# Single_PCB_-_IRM-10-5.net
KiCad netlist of a schematic drawn in EAGLE
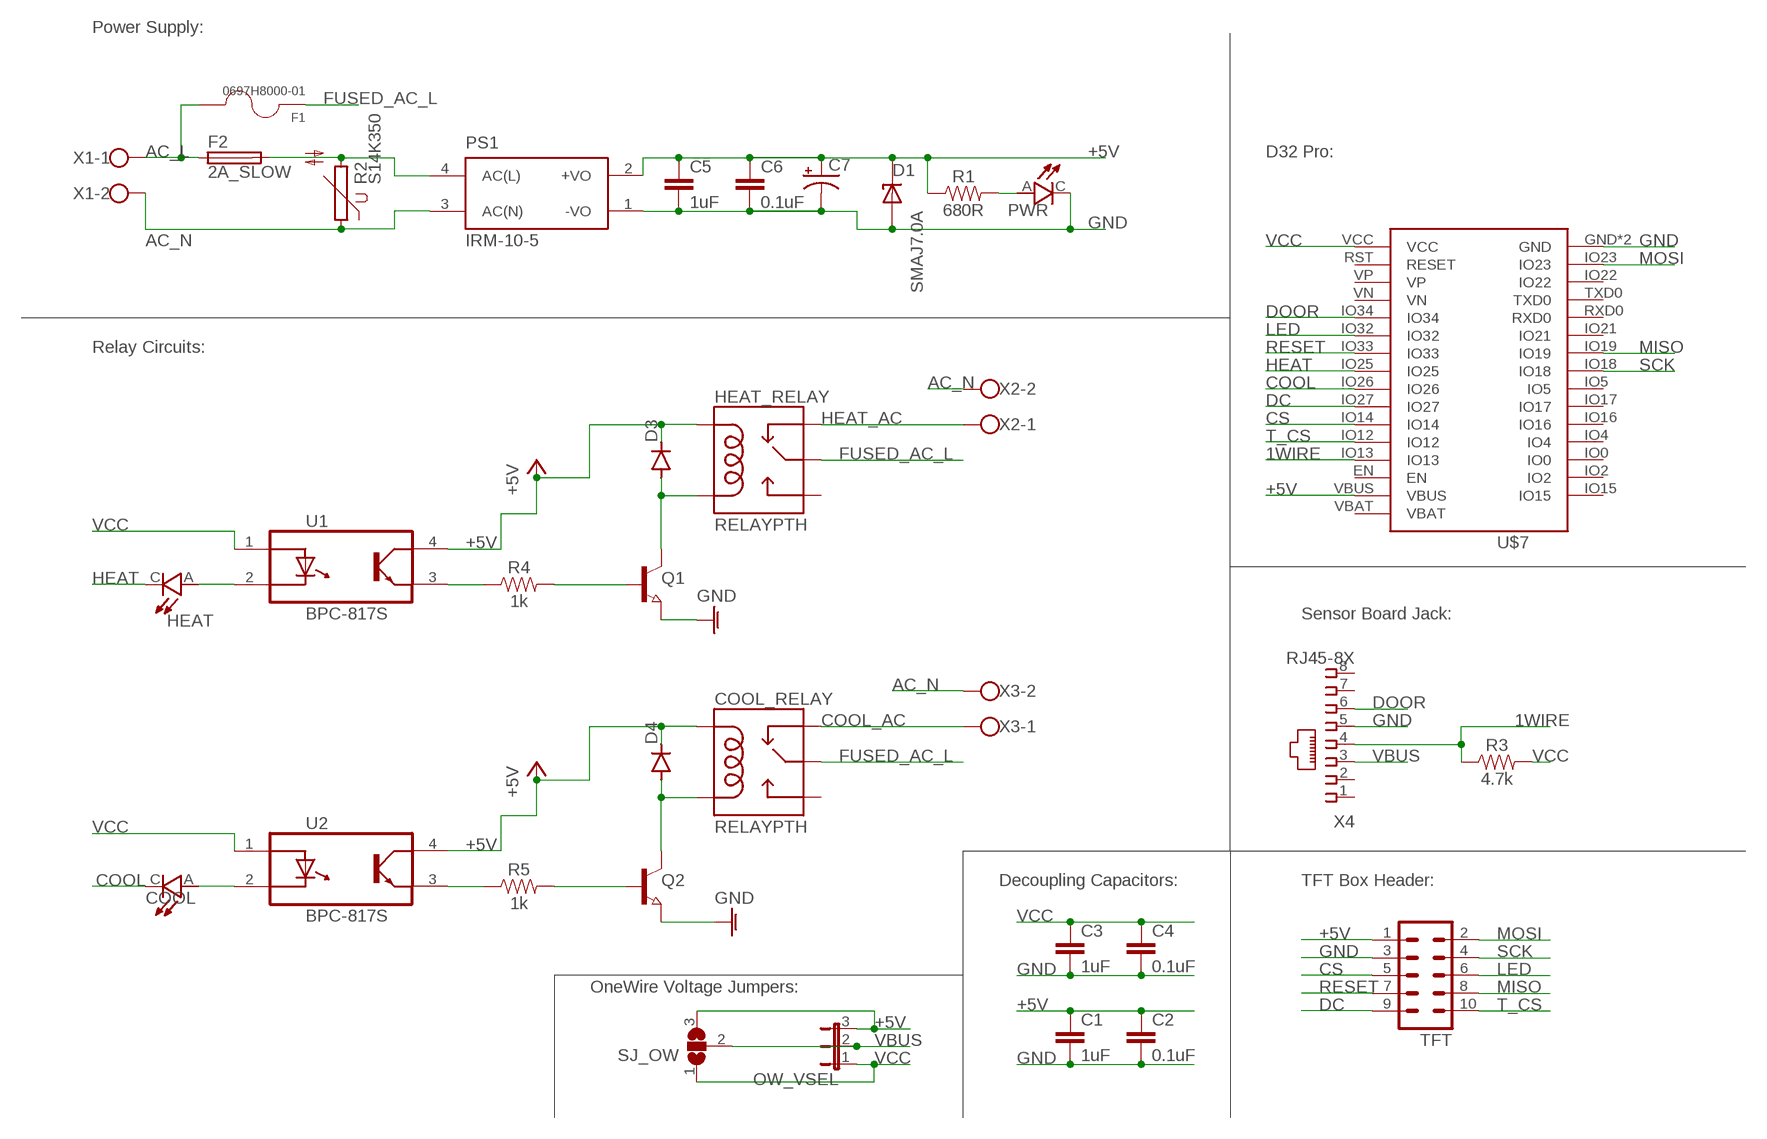
[diagram p0: schematic, sheet 1]

(export (version "E")
  (design (tool "Eeschema 10.0.6"))
  (components
    (comp (ref "C1")
      (value "1uF")
      (footprint "eagle-import:SMD-0805")
      (fields (field (name "LCSC_PART") "C28323"))
      (libsource (lib "eagle-import") (part "CAP_SMD0805"))
    )
    (comp (ref "C2")
      (value "0.1uF")
      (footprint "eagle-import:SMD-0805")
      (fields (field (name "LCSC_PART") "C49678"))
      (libsource (lib "eagle-import") (part "CAP_SMD0805"))
    )
    (comp (ref "C3")
      (value "1uF")
      (footprint "eagle-import:SMD-0805")
      (fields (field (name "LCSC_PART") "C28323"))
      (libsource (lib "eagle-import") (part "CAP_SMD0805"))
    )
    (comp (ref "C4")
      (value "0.1uF")
      (footprint "eagle-import:SMD-0805")
      (fields (field (name "LCSC_PART") "C49678"))
      (libsource (lib "eagle-import") (part "CAP_SMD0805"))
    )
    (comp (ref "C5")
      (value "1uF")
      (footprint "eagle-import:SMD-0805")
      (fields (field (name "LCSC_PART") "C28323"))
      (libsource (lib "eagle-import") (part "CAP_SMD0805"))
    )
    (comp (ref "C6")
      (value "0.1uF")
      (footprint "eagle-import:SMD-0805")
      (fields (field (name "LCSC_PART") "C49678"))
      (libsource (lib "eagle-import") (part "CAP_SMD0805"))
    )
    (comp (ref "C7")
      (value "220uF")
      (footprint "eagle-import:CAPPRD750W80D1600H2700")
      (fields (field (name "LCSC_PART") "C698141"))
      (libsource (lib "eagle-import") (part "220UF-POLAR220UF"))
    )
    (comp (ref "COOL")
      (value "LED_0603LED_SMD_0603")
      (footprint "eagle-import:LED_SMD_0603")
      (fields (field (name "LCSC_PART") "C2286") (field (name "LCSC_PART_1") "C2286"))
      (libsource (lib "eagle-import") (part "LED_0603LED_SMD_0603"))
    )
    (comp (ref "COOL_RELAY")
      (value "RELAYPTH")
      (footprint "eagle-import:SRD-05VDC-SL-C")
      (fields (field (name "LCSC_PART") "C35449"))
      (libsource (lib "eagle-import") (part "RELAYPTH"))
    )
    (comp (ref "D1")
      (value "SMAJ7.0A")
      (footprint "eagle-import:DIOM4325X250N")
      (fields (field (name "MF") "Littelfuse") (field (name "LCSC_PART") "C309904"))
      (libsource (lib "eagle-import") (part "SMAJ7.0A"))
    )
    (comp (ref "D3")
      (value "DIODE-DO214AC")
      (footprint "eagle-import:DO214AC")
      (fields (field (name "LCSC_PART") "C95872"))
      (libsource (lib "eagle-import") (part "DIODE-DO214AC"))
    )
    (comp (ref "D4")
      (value "DIODE-DO214AC")
      (footprint "eagle-import:DO214AC")
      (fields (field (name "LCSC_PART") "C95872"))
      (libsource (lib "eagle-import") (part "DIODE-DO214AC"))
    )
    (comp (ref "F1")
      (value "0697H8000-01")
      (footprint "eagle-import:FUSRR508W60L835T400H810")
      (fields (field (name "MF") "Bel Fuse") (field (name "LCSC_PART") "C3157783"))
      (libsource (lib "eagle-import") (part "0697H8000-01"))
    )
    (comp (ref "F2")
      (value "2A_SLOW")
      (footprint "eagle-import:FUSE_BK_PCE-5-R")
      (fields (field (name "LCSC_PART") "C3161740"))
      (libsource (lib "eagle-import") (part "FUSEFUSE_85_43"))
    )
    (comp (ref "HEAT")
      (value "LED_0603LED_SMD_0603")
      (footprint "eagle-import:LED_SMD_0603")
      (fields (field (name "LCSC_PART") "C2286") (field (name "LCSC_PART_1") "C2286"))
      (libsource (lib "eagle-import") (part "LED_0603LED_SMD_0603"))
    )
    (comp (ref "HEAT_RELAY")
      (value "RELAYPTH")
      (footprint "eagle-import:SRD-05VDC-SL-C")
      (fields (field (name "LCSC_PART") "C35449"))
      (libsource (lib "eagle-import") (part "RELAYPTH"))
    )
    (comp (ref "OW_VSEL")
      (value "JP2ENOLABEL")
      (footprint "eagle-import:JP2-NOLABEL")
      (fields (field (name "LCSC_PART") "C2937625"))
      (libsource (lib "eagle-import") (part "JP2ENOLABEL"))
    )
    (comp (ref "PS1")
      (value "IRM-10-5")
      (footprint "eagle-import:IRM-10_MWU")
      (fields (field (name "LCSC_PART") "C2857903"))
      (libsource (lib "eagle-import") (part "IRM-10-5-JB"))
    )
    (comp (ref "PWR")
      (value "LED_0603LED_SMD_0603")
      (footprint "eagle-import:LED_SMD_0603")
      (fields (field (name "LCSC_PART") "C2286") (field (name "LCSC_PART_1") "C2286"))
      (libsource (lib "eagle-import") (part "LED_0603LED_SMD_0603"))
    )
    (comp (ref "Q1")
      (value "NPN-TRANSISTOR_SOT23")
      (footprint "eagle-import:SOT23")
      (fields (field (name "LCSC_PART") "C20526"))
      (libsource (lib "eagle-import") (part "NPN-TRANSISTOR_SOT23"))
    )
    (comp (ref "Q2")
      (value "NPN-TRANSISTOR_SOT23")
      (footprint "eagle-import:SOT23")
      (fields (field (name "LCSC_PART") "C20526"))
      (libsource (lib "eagle-import") (part "NPN-TRANSISTOR_SOT23"))
    )
    (comp (ref "R1")
      (value "680R")
      (footprint "eagle-import:SMD-0805")
      (fields (field (name "LCSC_PART") "C17798"))
      (libsource (lib "eagle-import") (part "RES_SMD0805"))
    )
    (comp (ref "R2")
      (value "S14K350")
      (footprint "eagle-import:S10K350")
      (fields (field (name "LCSC_PART") "C78355"))
      (libsource (lib "eagle-import") (part "S10K350"))
    )
    (comp (ref "R3")
      (value "4.7k")
      (footprint "eagle-import:SMD-0805")
      (fields (field (name "LCSC_PART") "C17673"))
      (libsource (lib "eagle-import") (part "RES_SMD0805"))
    )
    (comp (ref "R4")
      (value "1k")
      (footprint "eagle-import:SMD-0805")
      (fields (field (name "LCSC_PART") "C17513"))
      (libsource (lib "eagle-import") (part "RES_SMD0805"))
    )
    (comp (ref "R5")
      (value "1k")
      (footprint "eagle-import:SMD-0805")
      (fields (field (name "LCSC_PART") "C17513"))
      (libsource (lib "eagle-import") (part "RES_SMD0805"))
    )
    (comp (ref "SJ_OW")
      (value "SJ2W")
      (footprint "eagle-import:SJ_2")
      (libsource (lib "eagle-import") (part "SJ2W"))
    )
    (comp (ref "TFT")
      (value "MA05-2")
      (footprint "eagle-import:MA05-2")
      (libsource (lib "eagle-import") (part "MA05-2"))
    )
    (comp (ref "U$7")
      (value "WEMOS-D32D32_PRO_NO-KEEPOUT")
      (footprint "eagle-import:D32_PRO_NO-KEEPOUT")
      (fields (field (name "LCSC_PART") "C18078137"))
      (libsource (lib "eagle-import") (part "WEMOS-D32D32_PRO_NO-KEEPOUT"))
    )
    (comp (ref "U1")
      (value "BPC-817S")
      (footprint "eagle-import:SOIC127P700X210-4N")
      (fields (field (name "LCSC_PART") "C106900"))
      (libsource (lib "eagle-import") (part "BPC-817S"))
    )
    (comp (ref "U2")
      (value "BPC-817S")
      (footprint "eagle-import:SOIC127P700X210-4N")
      (fields (field (name "LCSC_PART") "C106900"))
      (libsource (lib "eagle-import") (part "BPC-817S"))
    )
    (comp (ref "X1")
      (value "W237-102")
      (footprint "eagle-import:W237-102")
      (fields (field (name "MPN") "237-102"))
      (libsource (lib "eagle-import") (part "W237-102"))
    )
    (comp (ref "X2")
      (value "W237-102")
      (footprint "eagle-import:W237-102")
      (fields (field (name "MPN") "237-102"))
      (libsource (lib "eagle-import") (part "W237-102"))
    )
    (comp (ref "X3")
      (value "W237-102")
      (footprint "eagle-import:W237-102")
      (fields (field (name "MPN") "237-102"))
      (libsource (lib "eagle-import") (part "W237-102"))
    )
    (comp (ref "X4")
      (value "RJ45-8X")
      (footprint "eagle-import:RJ45-NO-SHIELD")
      (fields
        (field (name "LCSC_PART") "C3000197")
        (field (name "JLC_Y") "7.55")
        (field (name "LCSC_PART_1") "C3000197")
      )
      (libsource (lib "eagle-import") (part "RJ45-8X"))
    )
  )
  (nets
    (net (code "1") (name "+5V") (class "Default")
      (node (ref "C1") (pin "1") (pinfunction "1_1") (pintype "passive"))
      (node (ref "C2") (pin "1") (pinfunction "1_1") (pintype "passive"))
      (node (ref "C5") (pin "1") (pinfunction "1_1") (pintype "passive"))
      (node (ref "C6") (pin "1") (pinfunction "1_1") (pintype "passive"))
      (node (ref "C7") (pin "2") (pinfunction "+_2") (pintype "passive"))
      (node (ref "COOL_RELAY") (pin "COIL1") (pinfunction "COIL1_COIL1") (pintype "bidirectional"))
      (node (ref "D1") (pin "C") (pinfunction "C_C") (pintype "passive"))
      (node (ref "D3") (pin "C") (pinfunction "C_C") (pintype "passive"))
      (node (ref "D4") (pin "C") (pinfunction "C_C") (pintype "passive"))
      (node (ref "HEAT_RELAY") (pin "COIL1") (pinfunction "COIL1_COIL1") (pintype "bidirectional"))
      (node (ref "OW_VSEL") (pin "3") (pinfunction "3_3") (pintype "passive"))
      (node (ref "PS1") (pin "2") (pinfunction "+VO_2") (pintype "output"))
      (node (ref "R1") (pin "1") (pinfunction "1_1") (pintype "passive"))
      (node (ref "SJ_OW") (pin "3") (pinfunction "3_3") (pintype "passive"))
      (node (ref "TFT") (pin "1") (pinfunction "1_1") (pintype "passive"))
      (node (ref "U$7") (pin "VBUS") (pinfunction "VBUS_VBUS") (pintype "bidirectional"))
      (node (ref "U1") (pin "4") (pinfunction "CO_4") (pintype "passive"))
      (node (ref "U2") (pin "4") (pinfunction "CO_4") (pintype "passive"))
    )
    (net (code "2") (name "/1WIRE") (class "Default")
      (node (ref "R3") (pin "1") (pinfunction "1_1") (pintype "passive"))
      (node (ref "U$7") (pin "IO13") (pinfunction "IO13_IO13") (pintype "bidirectional"))
      (node (ref "X4") (pin "4") (pinfunction "4_4") (pintype "passive"))
    )
    (net (code "3") (name "/AC_L") (class "Default")
      (node (ref "F1") (pin "2") (pinfunction "2_2") (pintype "passive"))
      (node (ref "F2") (pin "1") (pinfunction "1_1") (pintype "passive"))
      (node (ref "X1") (pin "1") (pinfunction "KL_1") (pintype "passive"))
    )
    (net (code "4") (name "/AC_N") (class "Default")
      (node (ref "PS1") (pin "3") (pinfunction "AC(N)_3") (pintype "input"))
      (node (ref "R2") (pin "1") (pinfunction "1_1") (pintype "passive"))
      (node (ref "X1") (pin "2") (pinfunction "KL_2") (pintype "passive"))
      (node (ref "X2") (pin "2") (pinfunction "KL_2") (pintype "passive"))
      (node (ref "X3") (pin "2") (pinfunction "KL_2") (pintype "passive"))
    )
    (net (code "5") (name "/COOL") (class "Default")
      (node (ref "COOL") (pin "C") (pinfunction "C_C") (pintype "passive"))
      (node (ref "U$7") (pin "IO26") (pinfunction "IO26_IO26") (pintype "bidirectional"))
    )
    (net (code "6") (name "/COOL_AC") (class "Default")
      (node (ref "COOL_RELAY") (pin "SWCLOSED") (pinfunction "SWCLOSE_SWCLOSED") (pintype "bidirectional"))
      (node (ref "X3") (pin "1") (pinfunction "KL_1") (pintype "passive"))
    )
    (net (code "7") (name "/CS") (class "Default")
      (node (ref "TFT") (pin "5") (pinfunction "5_5") (pintype "passive"))
      (node (ref "U$7") (pin "IO14") (pinfunction "IO14_IO14") (pintype "bidirectional"))
    )
    (net (code "8") (name "/DC") (class "Default")
      (node (ref "TFT") (pin "9") (pinfunction "9_9") (pintype "passive"))
      (node (ref "U$7") (pin "IO27") (pinfunction "IO27_IO27") (pintype "bidirectional"))
    )
    (net (code "9") (name "/DOOR") (class "Default")
      (node (ref "U$7") (pin "IO34") (pinfunction "IO34_IO34") (pintype "bidirectional"))
      (node (ref "X4") (pin "6") (pinfunction "6_6") (pintype "passive"))
    )
    (net (code "10") (name "/FUSED_AC_L") (class "Default")
      (node (ref "COOL_RELAY") (pin "SWCOMMON") (pinfunction "SWCOMMON_SWCOMMON") (pintype "bidirectional"))
      (node (ref "F1") (pin "1") (pinfunction "1_1") (pintype "passive"))
      (node (ref "HEAT_RELAY") (pin "SWCOMMON") (pinfunction "SWCOMMON_SWCOMMON") (pintype "bidirectional"))
    )
    (net (code "11") (name "/HEAT") (class "Default")
      (node (ref "HEAT") (pin "C") (pinfunction "C_C") (pintype "passive"))
      (node (ref "U$7") (pin "IO25") (pinfunction "IO25_IO25") (pintype "bidirectional"))
    )
    (net (code "12") (name "/HEAT_AC") (class "Default")
      (node (ref "HEAT_RELAY") (pin "SWCLOSED") (pinfunction "SWCLOSE_SWCLOSED") (pintype "bidirectional"))
      (node (ref "X2") (pin "1") (pinfunction "KL_1") (pintype "passive"))
    )
    (net (code "13") (name "/LED") (class "Default")
      (node (ref "TFT") (pin "6") (pinfunction "6_6") (pintype "passive"))
      (node (ref "U$7") (pin "IO32") (pinfunction "IO32_IO32") (pintype "bidirectional"))
    )
    (net (code "14") (name "/MISO") (class "Default")
      (node (ref "TFT") (pin "8") (pinfunction "8_8") (pintype "passive"))
      (node (ref "U$7") (pin "IO19") (pinfunction "IO19_IO19") (pintype "bidirectional"))
    )
    (net (code "15") (name "/MOSI") (class "Default")
      (node (ref "TFT") (pin "2") (pinfunction "2_2") (pintype "passive"))
      (node (ref "U$7") (pin "IO23") (pinfunction "IO23_IO23") (pintype "bidirectional"))
    )
    (net (code "16") (name "/RESET") (class "Default")
      (node (ref "TFT") (pin "7") (pinfunction "7_7") (pintype "passive"))
      (node (ref "U$7") (pin "IO33") (pinfunction "IO33_IO33") (pintype "bidirectional"))
    )
    (net (code "17") (name "/SCK") (class "Default")
      (node (ref "TFT") (pin "4") (pinfunction "4_4") (pintype "passive"))
      (node (ref "U$7") (pin "IO18") (pinfunction "IO18_IO18") (pintype "bidirectional"))
    )
    (net (code "18") (name "/T_CS") (class "Default")
      (node (ref "TFT") (pin "10") (pinfunction "10_10") (pintype "passive"))
      (node (ref "U$7") (pin "IO12") (pinfunction "IO12_IO12") (pintype "bidirectional"))
    )
    (net (code "19") (name "/VBUS") (class "Default")
      (node (ref "OW_VSEL") (pin "2") (pinfunction "2_2") (pintype "passive"))
      (node (ref "SJ_OW") (pin "2") (pinfunction "2_2") (pintype "passive"))
      (node (ref "X4") (pin "3") (pinfunction "3_3") (pintype "passive"))
    )
    (net (code "20") (name "/VCC") (class "Default")
      (node (ref "C3") (pin "1") (pinfunction "1_1") (pintype "passive"))
      (node (ref "C4") (pin "1") (pinfunction "1_1") (pintype "passive"))
      (node (ref "OW_VSEL") (pin "1") (pinfunction "1_1") (pintype "passive"))
      (node (ref "R3") (pin "2") (pinfunction "2_2") (pintype "passive"))
      (node (ref "SJ_OW") (pin "1") (pinfunction "1_1") (pintype "passive"))
      (node (ref "U$7") (pin "VCC") (pinfunction "VCC_VCC") (pintype "power_in"))
      (node (ref "U1") (pin "1") (pinfunction "A_1") (pintype "passive"))
      (node (ref "U2") (pin "1") (pinfunction "A_1") (pintype "passive"))
    )
    (net (code "21") (name "GNDA") (class "Default")
      (node (ref "C1") (pin "2") (pinfunction "2_2") (pintype "passive"))
      (node (ref "C2") (pin "2") (pinfunction "2_2") (pintype "passive"))
      (node (ref "C3") (pin "2") (pinfunction "2_2") (pintype "passive"))
      (node (ref "C4") (pin "2") (pinfunction "2_2") (pintype "passive"))
      (node (ref "C5") (pin "2") (pinfunction "2_2") (pintype "passive"))
      (node (ref "C6") (pin "2") (pinfunction "2_2") (pintype "passive"))
      (node (ref "C7") (pin "1") (pinfunction "-_1") (pintype "passive"))
      (node (ref "D1") (pin "A") (pinfunction "A_A") (pintype "passive"))
      (node (ref "PS1") (pin "1") (pinfunction "-VO_1") (pintype "output"))
      (node (ref "PWR") (pin "C") (pinfunction "C_C") (pintype "passive"))
      (node (ref "Q1") (pin "2") (pinfunction "E_2") (pintype "passive"))
      (node (ref "Q2") (pin "2") (pinfunction "E_2") (pintype "passive"))
      (node (ref "TFT") (pin "3") (pinfunction "3_3") (pintype "passive"))
      (node (ref "U$7") (pin "GND") (pinfunction "GND_GND") (pintype "power_in"))
      (node (ref "U$7") (pin "GND2") (pinfunction "GND_GND2") (pintype "power_in"))
      (node (ref "X4") (pin "5") (pinfunction "5_5") (pintype "passive"))
    )
    (net (code "22") (name "Net-(PS1-AC(L))") (class "Default")
      (node (ref "F2") (pin "2") (pinfunction "2_2") (pintype "passive"))
      (node (ref "PS1") (pin "4") (pinfunction "AC(L)_4") (pintype "input"))
      (node (ref "R2") (pin "2") (pinfunction "2_2") (pintype "passive"))
    )
    (net (code "23") (name "Net-(PWR-PadA)") (class "Default")
      (node (ref "PWR") (pin "A") (pinfunction "A_A") (pintype "passive"))
      (node (ref "R1") (pin "2") (pinfunction "2_2") (pintype "passive"))
    )
    (net (code "24") (name "Net-(Q1-B)") (class "Default")
      (node (ref "Q1") (pin "1") (pinfunction "B_1") (pintype "passive"))
      (node (ref "R4") (pin "2") (pinfunction "2_2") (pintype "passive"))
    )
    (net (code "25") (name "Net-(Q1-C)") (class "Default")
      (node (ref "D3") (pin "A") (pinfunction "A_A") (pintype "passive"))
      (node (ref "HEAT_RELAY") (pin "COIL0") (pinfunction "COIL0_COIL0") (pintype "bidirectional"))
      (node (ref "Q1") (pin "3") (pinfunction "C_3") (pintype "passive"))
    )
    (net (code "26") (name "Net-(Q2-B)") (class "Default")
      (node (ref "Q2") (pin "1") (pinfunction "B_1") (pintype "passive"))
      (node (ref "R5") (pin "2") (pinfunction "2_2") (pintype "passive"))
    )
    (net (code "27") (name "Net-(Q2-C)") (class "Default")
      (node (ref "COOL_RELAY") (pin "COIL0") (pinfunction "COIL0_COIL0") (pintype "bidirectional"))
      (node (ref "D4") (pin "A") (pinfunction "A_A") (pintype "passive"))
      (node (ref "Q2") (pin "3") (pinfunction "C_3") (pintype "passive"))
    )
    (net (code "28") (name "Net-(U1-C)") (class "Default")
      (node (ref "HEAT") (pin "A") (pinfunction "A_A") (pintype "passive"))
      (node (ref "U1") (pin "2") (pinfunction "C_2") (pintype "passive"))
    )
    (net (code "29") (name "Net-(U1-E)") (class "Default")
      (node (ref "R4") (pin "1") (pinfunction "1_1") (pintype "passive"))
      (node (ref "U1") (pin "3") (pinfunction "E_3") (pintype "passive"))
    )
    (net (code "30") (name "Net-(U2-C)") (class "Default")
      (node (ref "COOL") (pin "A") (pinfunction "A_A") (pintype "passive"))
      (node (ref "U2") (pin "2") (pinfunction "C_2") (pintype "passive"))
    )
    (net (code "31") (name "Net-(U2-E)") (class "Default")
      (node (ref "R5") (pin "1") (pinfunction "1_1") (pintype "passive"))
      (node (ref "U2") (pin "3") (pinfunction "E_3") (pintype "passive"))
    )
    (net (code "32") (name "unconnected-(COOL_RELAY-PadSWOPEN)") (class "Default")
      (node (ref "COOL_RELAY") (pin "SWOPEN") (pinfunction "SWOPEN_SWOPEN") (pintype "bidirectional"))
    )
    (net (code "33") (name "unconnected-(HEAT_RELAY-PadSWOPEN)") (class "Default")
      (node (ref "HEAT_RELAY") (pin "SWOPEN") (pinfunction "SWOPEN_SWOPEN") (pintype "bidirectional"))
    )
    (net (code "34") (name "unconnected-(U$7-PadEN)") (class "Default")
      (node (ref "U$7") (pin "EN") (pinfunction "EN_EN") (pintype "bidirectional"))
    )
    (net (code "35") (name "unconnected-(U$7-PadIO0)") (class "Default")
      (node (ref "U$7") (pin "IO0") (pinfunction "IO0_IO0") (pintype "bidirectional"))
    )
    (net (code "36") (name "unconnected-(U$7-PadIO2)") (class "Default")
      (node (ref "U$7") (pin "IO2") (pinfunction "IO2_IO2") (pintype "bidirectional"))
    )
    (net (code "37") (name "unconnected-(U$7-PadIO4)") (class "Default")
      (node (ref "U$7") (pin "IO4") (pinfunction "IO4_IO4") (pintype "bidirectional"))
    )
    (net (code "38") (name "unconnected-(U$7-PadIO5)") (class "Default")
      (node (ref "U$7") (pin "IO5") (pinfunction "IO5_IO5") (pintype "bidirectional"))
    )
    (net (code "39") (name "unconnected-(U$7-PadIO15)") (class "Default")
      (node (ref "U$7") (pin "IO15") (pinfunction "IO15_IO15") (pintype "bidirectional"))
    )
    (net (code "40") (name "unconnected-(U$7-PadIO16)") (class "Default")
      (node (ref "U$7") (pin "IO16") (pinfunction "IO16_IO16") (pintype "bidirectional"))
    )
    (net (code "41") (name "unconnected-(U$7-PadIO17)") (class "Default")
      (node (ref "U$7") (pin "IO17") (pinfunction "IO17_IO17") (pintype "bidirectional"))
    )
    (net (code "42") (name "unconnected-(U$7-PadIO21)") (class "Default")
      (node (ref "U$7") (pin "IO21") (pinfunction "IO21_IO21") (pintype "bidirectional"))
    )
    (net (code "43") (name "unconnected-(U$7-PadIO22)") (class "Default")
      (node (ref "U$7") (pin "IO22") (pinfunction "IO22_IO22") (pintype "bidirectional"))
    )
    (net (code "44") (name "unconnected-(U$7-PadRXD0)") (class "Default")
      (node (ref "U$7") (pin "RXD0") (pinfunction "RXD0_RXD0") (pintype "input"))
    )
    (net (code "45") (name "unconnected-(U$7-PadTXD0)") (class "Default")
      (node (ref "U$7") (pin "TXD0") (pinfunction "TXD0_TXD0") (pintype "output"))
    )
    (net (code "46") (name "unconnected-(U$7-PadVBAT)") (class "Default")
      (node (ref "U$7") (pin "VBAT") (pinfunction "VBAT_VBAT") (pintype "bidirectional"))
    )
    (net (code "47") (name "unconnected-(U$7-PadVN)") (class "Default")
      (node (ref "U$7") (pin "VN") (pinfunction "VN_VN") (pintype "bidirectional"))
    )
    (net (code "48") (name "unconnected-(U$7-PadVP)") (class "Default")
      (node (ref "U$7") (pin "VP") (pinfunction "VP_VP") (pintype "bidirectional"))
    )
    (net (code "49") (name "unconnected-(U$7-RESET-PadRST)") (class "Default")
      (node (ref "U$7") (pin "RST") (pinfunction "RESET_RST") (pintype "bidirectional"))
    )
    (net (code "50") (name "unconnected-(X4-Pad1)") (class "Default")
      (node (ref "X4") (pin "1") (pinfunction "1_1") (pintype "passive"))
    )
    (net (code "51") (name "unconnected-(X4-Pad2)") (class "Default")
      (node (ref "X4") (pin "2") (pinfunction "2_2") (pintype "passive"))
    )
    (net (code "52") (name "unconnected-(X4-Pad7)") (class "Default")
      (node (ref "X4") (pin "7") (pinfunction "7_7") (pintype "passive"))
    )
    (net (code "53") (name "unconnected-(X4-Pad8)") (class "Default")
      (node (ref "X4") (pin "8") (pinfunction "8_8") (pintype "passive"))
    )
  )
)
